# spectrum.net
KiCad netlist of a schematic drawn in EAGLE
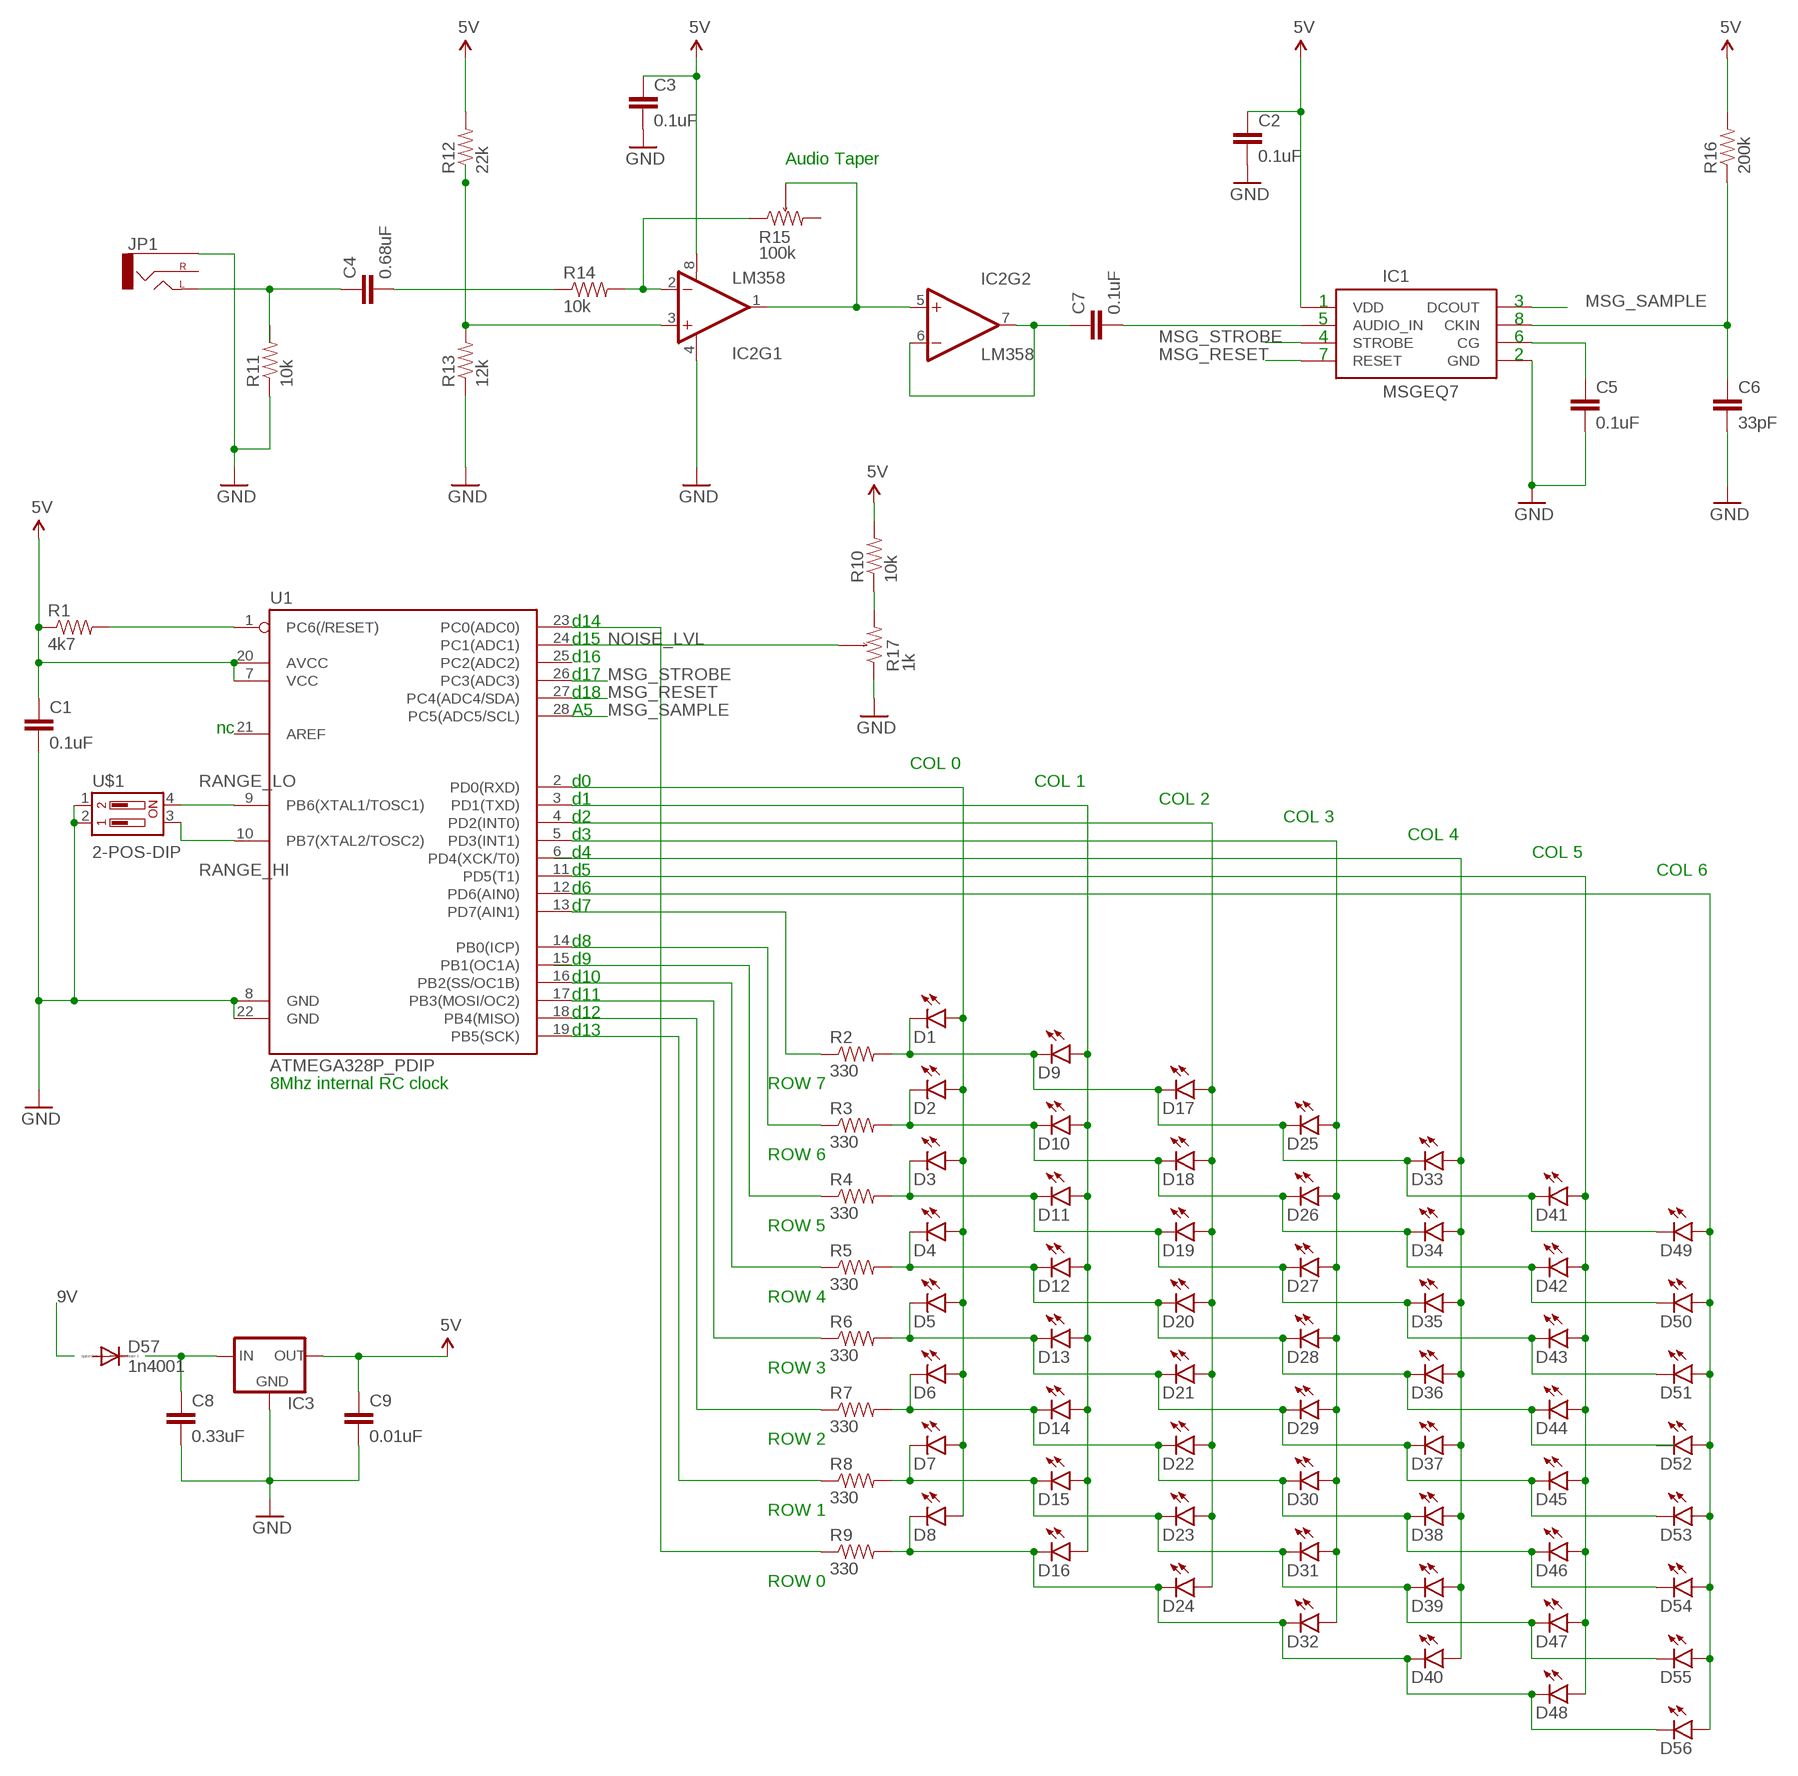
[diagram p0: schematic, sheet 1]

(export (version "E")
  (design (tool "Eeschema 10.0.6"))
  (components
    (comp (ref "C1")
      (value "0.1uF")
      (footprint "eagle-import:0402-CAP")
      (libsource (lib "eagle-import") (part "CAP0402-CAP"))
    )
    (comp (ref "C2")
      (value "0.1uF")
      (footprint "eagle-import:0402-CAP")
      (libsource (lib "eagle-import") (part "CAP0402-CAP"))
    )
    (comp (ref "C3")
      (value "0.1uF")
      (footprint "eagle-import:0402-CAP")
      (libsource (lib "eagle-import") (part "CAP0402-CAP"))
    )
    (comp (ref "C4")
      (value "0.68uF")
      (footprint "eagle-import:0402-CAP")
      (libsource (lib "eagle-import") (part "CAP0402-CAP"))
    )
    (comp (ref "C5")
      (value "0.1uF")
      (footprint "eagle-import:0402-CAP")
      (libsource (lib "eagle-import") (part "CAP0402-CAP"))
    )
    (comp (ref "C6")
      (value "33pF")
      (footprint "eagle-import:0402-CAP")
      (libsource (lib "eagle-import") (part "CAP0402-CAP"))
    )
    (comp (ref "C7")
      (value "0.1uF")
      (footprint "eagle-import:0402-CAP")
      (libsource (lib "eagle-import") (part "CAP0402-CAP"))
    )
    (comp (ref "C8")
      (value "0.33uF")
      (footprint "eagle-import:0402-CAP")
      (libsource (lib "eagle-import") (part "CAP0402-CAP"))
    )
    (comp (ref "C9")
      (value "0.01uF")
      (footprint "eagle-import:0402-CAP")
      (libsource (lib "eagle-import") (part "CAP0402-CAP"))
    )
    (comp (ref "D1")
      (value "LED5MM")
      (footprint "eagle-import:LED5MM")
      (libsource (lib "eagle-import") (part "LED5MM"))
    )
    (comp (ref "D2")
      (value "LED5MM")
      (footprint "eagle-import:LED5MM")
      (libsource (lib "eagle-import") (part "LED5MM"))
    )
    (comp (ref "D3")
      (value "LED5MM")
      (footprint "eagle-import:LED5MM")
      (libsource (lib "eagle-import") (part "LED5MM"))
    )
    (comp (ref "D4")
      (value "LED5MM")
      (footprint "eagle-import:LED5MM")
      (libsource (lib "eagle-import") (part "LED5MM"))
    )
    (comp (ref "D5")
      (value "LED5MM")
      (footprint "eagle-import:LED5MM")
      (libsource (lib "eagle-import") (part "LED5MM"))
    )
    (comp (ref "D6")
      (value "LED5MM")
      (footprint "eagle-import:LED5MM")
      (libsource (lib "eagle-import") (part "LED5MM"))
    )
    (comp (ref "D7")
      (value "LED5MM")
      (footprint "eagle-import:LED5MM")
      (libsource (lib "eagle-import") (part "LED5MM"))
    )
    (comp (ref "D8")
      (value "LED5MM")
      (footprint "eagle-import:LED5MM")
      (libsource (lib "eagle-import") (part "LED5MM"))
    )
    (comp (ref "D9")
      (value "LED5MM")
      (footprint "eagle-import:LED5MM")
      (libsource (lib "eagle-import") (part "LED5MM"))
    )
    (comp (ref "D10")
      (value "LED5MM")
      (footprint "eagle-import:LED5MM")
      (libsource (lib "eagle-import") (part "LED5MM"))
    )
    (comp (ref "D11")
      (value "LED5MM")
      (footprint "eagle-import:LED5MM")
      (libsource (lib "eagle-import") (part "LED5MM"))
    )
    (comp (ref "D12")
      (value "LED5MM")
      (footprint "eagle-import:LED5MM")
      (libsource (lib "eagle-import") (part "LED5MM"))
    )
    (comp (ref "D13")
      (value "LED5MM")
      (footprint "eagle-import:LED5MM")
      (libsource (lib "eagle-import") (part "LED5MM"))
    )
    (comp (ref "D14")
      (value "LED5MM")
      (footprint "eagle-import:LED5MM")
      (libsource (lib "eagle-import") (part "LED5MM"))
    )
    (comp (ref "D15")
      (value "LED5MM")
      (footprint "eagle-import:LED5MM")
      (libsource (lib "eagle-import") (part "LED5MM"))
    )
    (comp (ref "D16")
      (value "LED5MM")
      (footprint "eagle-import:LED5MM")
      (libsource (lib "eagle-import") (part "LED5MM"))
    )
    (comp (ref "D17")
      (value "LED5MM")
      (footprint "eagle-import:LED5MM")
      (libsource (lib "eagle-import") (part "LED5MM"))
    )
    (comp (ref "D18")
      (value "LED5MM")
      (footprint "eagle-import:LED5MM")
      (libsource (lib "eagle-import") (part "LED5MM"))
    )
    (comp (ref "D19")
      (value "LED5MM")
      (footprint "eagle-import:LED5MM")
      (libsource (lib "eagle-import") (part "LED5MM"))
    )
    (comp (ref "D20")
      (value "LED5MM")
      (footprint "eagle-import:LED5MM")
      (libsource (lib "eagle-import") (part "LED5MM"))
    )
    (comp (ref "D21")
      (value "LED5MM")
      (footprint "eagle-import:LED5MM")
      (libsource (lib "eagle-import") (part "LED5MM"))
    )
    (comp (ref "D22")
      (value "LED5MM")
      (footprint "eagle-import:LED5MM")
      (libsource (lib "eagle-import") (part "LED5MM"))
    )
    (comp (ref "D23")
      (value "LED5MM")
      (footprint "eagle-import:LED5MM")
      (libsource (lib "eagle-import") (part "LED5MM"))
    )
    (comp (ref "D24")
      (value "LED5MM")
      (footprint "eagle-import:LED5MM")
      (libsource (lib "eagle-import") (part "LED5MM"))
    )
    (comp (ref "D25")
      (value "LED5MM")
      (footprint "eagle-import:LED5MM")
      (libsource (lib "eagle-import") (part "LED5MM"))
    )
    (comp (ref "D26")
      (value "LED5MM")
      (footprint "eagle-import:LED5MM")
      (libsource (lib "eagle-import") (part "LED5MM"))
    )
    (comp (ref "D27")
      (value "LED5MM")
      (footprint "eagle-import:LED5MM")
      (libsource (lib "eagle-import") (part "LED5MM"))
    )
    (comp (ref "D28")
      (value "LED5MM")
      (footprint "eagle-import:LED5MM")
      (libsource (lib "eagle-import") (part "LED5MM"))
    )
    (comp (ref "D29")
      (value "LED5MM")
      (footprint "eagle-import:LED5MM")
      (libsource (lib "eagle-import") (part "LED5MM"))
    )
    (comp (ref "D30")
      (value "LED5MM")
      (footprint "eagle-import:LED5MM")
      (libsource (lib "eagle-import") (part "LED5MM"))
    )
    (comp (ref "D31")
      (value "LED5MM")
      (footprint "eagle-import:LED5MM")
      (libsource (lib "eagle-import") (part "LED5MM"))
    )
    (comp (ref "D32")
      (value "LED5MM")
      (footprint "eagle-import:LED5MM")
      (libsource (lib "eagle-import") (part "LED5MM"))
    )
    (comp (ref "D33")
      (value "LED5MM")
      (footprint "eagle-import:LED5MM")
      (libsource (lib "eagle-import") (part "LED5MM"))
    )
    (comp (ref "D34")
      (value "LED5MM")
      (footprint "eagle-import:LED5MM")
      (libsource (lib "eagle-import") (part "LED5MM"))
    )
    (comp (ref "D35")
      (value "LED5MM")
      (footprint "eagle-import:LED5MM")
      (libsource (lib "eagle-import") (part "LED5MM"))
    )
    (comp (ref "D36")
      (value "LED5MM")
      (footprint "eagle-import:LED5MM")
      (libsource (lib "eagle-import") (part "LED5MM"))
    )
    (comp (ref "D37")
      (value "LED5MM")
      (footprint "eagle-import:LED5MM")
      (libsource (lib "eagle-import") (part "LED5MM"))
    )
    (comp (ref "D38")
      (value "LED5MM")
      (footprint "eagle-import:LED5MM")
      (libsource (lib "eagle-import") (part "LED5MM"))
    )
    (comp (ref "D39")
      (value "LED5MM")
      (footprint "eagle-import:LED5MM")
      (libsource (lib "eagle-import") (part "LED5MM"))
    )
    (comp (ref "D40")
      (value "LED5MM")
      (footprint "eagle-import:LED5MM")
      (libsource (lib "eagle-import") (part "LED5MM"))
    )
    (comp (ref "D41")
      (value "LED5MM")
      (footprint "eagle-import:LED5MM")
      (libsource (lib "eagle-import") (part "LED5MM"))
    )
    (comp (ref "D42")
      (value "LED5MM")
      (footprint "eagle-import:LED5MM")
      (libsource (lib "eagle-import") (part "LED5MM"))
    )
    (comp (ref "D43")
      (value "LED5MM")
      (footprint "eagle-import:LED5MM")
      (libsource (lib "eagle-import") (part "LED5MM"))
    )
    (comp (ref "D44")
      (value "LED5MM")
      (footprint "eagle-import:LED5MM")
      (libsource (lib "eagle-import") (part "LED5MM"))
    )
    (comp (ref "D45")
      (value "LED5MM")
      (footprint "eagle-import:LED5MM")
      (libsource (lib "eagle-import") (part "LED5MM"))
    )
    (comp (ref "D46")
      (value "LED5MM")
      (footprint "eagle-import:LED5MM")
      (libsource (lib "eagle-import") (part "LED5MM"))
    )
    (comp (ref "D47")
      (value "LED5MM")
      (footprint "eagle-import:LED5MM")
      (libsource (lib "eagle-import") (part "LED5MM"))
    )
    (comp (ref "D48")
      (value "LED5MM")
      (footprint "eagle-import:LED5MM")
      (libsource (lib "eagle-import") (part "LED5MM"))
    )
    (comp (ref "D49")
      (value "LED5MM")
      (footprint "eagle-import:LED5MM")
      (libsource (lib "eagle-import") (part "LED5MM"))
    )
    (comp (ref "D50")
      (value "LED5MM")
      (footprint "eagle-import:LED5MM")
      (libsource (lib "eagle-import") (part "LED5MM"))
    )
    (comp (ref "D51")
      (value "LED5MM")
      (footprint "eagle-import:LED5MM")
      (libsource (lib "eagle-import") (part "LED5MM"))
    )
    (comp (ref "D52")
      (value "LED5MM")
      (footprint "eagle-import:LED5MM")
      (libsource (lib "eagle-import") (part "LED5MM"))
    )
    (comp (ref "D53")
      (value "LED5MM")
      (footprint "eagle-import:LED5MM")
      (libsource (lib "eagle-import") (part "LED5MM"))
    )
    (comp (ref "D54")
      (value "LED5MM")
      (footprint "eagle-import:LED5MM")
      (libsource (lib "eagle-import") (part "LED5MM"))
    )
    (comp (ref "D55")
      (value "LED5MM")
      (footprint "eagle-import:LED5MM")
      (libsource (lib "eagle-import") (part "LED5MM"))
    )
    (comp (ref "D56")
      (value "LED5MM")
      (footprint "eagle-import:LED5MM")
      (libsource (lib "eagle-import") (part "LED5MM"))
    )
    (comp (ref "D57")
      (value "1n4001")
      (footprint "eagle-import:DO41-10")
      (libsource (lib "eagle-import") (part "1N4004"))
    )
    (comp (ref "IC1")
      (value "MSGEQ7DIL")
      (footprint "eagle-import:DIL-08")
      (libsource (lib "eagle-import") (part "MSGEQ7DIL"))
    )
    (comp (ref "IC2")
      (value "LM358")
      (footprint "eagle-import:DIP08")
      (libsource (lib "eagle-import") (part "LM358"))
    )
    (comp (ref "IC3")
      (value "78LXX")
      (footprint "eagle-import:78LXX")
      (libsource (lib "eagle-import") (part "78LXX"))
    )
    (comp (ref "JP1")
      (value "AUDIO-JACK1:1")
      (footprint "eagle-import:STEREOJACK2.5MM")
      (libsource (lib "eagle-import") (part "AUDIO-JACK1{colon}1"))
    )
    (comp (ref "R1")
      (value "4k7")
      (footprint "eagle-import:0402-RES")
      (libsource (lib "eagle-import") (part "RESISTOR0402-RES"))
    )
    (comp (ref "R2")
      (value "330")
      (footprint "eagle-import:0402-RES")
      (libsource (lib "eagle-import") (part "RESISTOR0402-RES"))
    )
    (comp (ref "R3")
      (value "330")
      (footprint "eagle-import:0402-RES")
      (libsource (lib "eagle-import") (part "RESISTOR0402-RES"))
    )
    (comp (ref "R4")
      (value "330")
      (footprint "eagle-import:0402-RES")
      (libsource (lib "eagle-import") (part "RESISTOR0402-RES"))
    )
    (comp (ref "R5")
      (value "330")
      (footprint "eagle-import:0402-RES")
      (libsource (lib "eagle-import") (part "RESISTOR0402-RES"))
    )
    (comp (ref "R6")
      (value "330")
      (footprint "eagle-import:0402-RES")
      (libsource (lib "eagle-import") (part "RESISTOR0402-RES"))
    )
    (comp (ref "R7")
      (value "330")
      (footprint "eagle-import:0402-RES")
      (libsource (lib "eagle-import") (part "RESISTOR0402-RES"))
    )
    (comp (ref "R8")
      (value "330")
      (footprint "eagle-import:0402-RES")
      (libsource (lib "eagle-import") (part "RESISTOR0402-RES"))
    )
    (comp (ref "R9")
      (value "330")
      (footprint "eagle-import:0402-RES")
      (libsource (lib "eagle-import") (part "RESISTOR0402-RES"))
    )
    (comp (ref "R10")
      (value "10k")
      (footprint "eagle-import:0402-RES")
      (libsource (lib "eagle-import") (part "RESISTOR0402-RES"))
    )
    (comp (ref "R11")
      (value "10k")
      (footprint "eagle-import:0402-RES")
      (libsource (lib "eagle-import") (part "RESISTOR0402-RES"))
    )
    (comp (ref "R12")
      (value "22k")
      (footprint "eagle-import:0402-RES")
      (libsource (lib "eagle-import") (part "RESISTOR0402-RES"))
    )
    (comp (ref "R13")
      (value "12k")
      (footprint "eagle-import:0402-RES")
      (libsource (lib "eagle-import") (part "RESISTOR0402-RES"))
    )
    (comp (ref "R14")
      (value "10k")
      (footprint "eagle-import:0402-RES")
      (libsource (lib "eagle-import") (part "RESISTOR0402-RES"))
    )
    (comp (ref "R15")
      (value "100k")
      (footprint "eagle-import:0603-ARV")
      (libsource (lib "eagle-import") (part "POTENTIOMETER"))
    )
    (comp (ref "R16")
      (value "200k")
      (footprint "eagle-import:0402-RES")
      (libsource (lib "eagle-import") (part "RESISTOR0402-RES"))
    )
    (comp (ref "R17")
      (value "1k")
      (footprint "eagle-import:0603-ARV")
      (libsource (lib "eagle-import") (part "POTENTIOMETER"))
    )
    (comp (ref "U$1")
      (value "2-POS-DIP")
      (footprint "eagle-import:CHS-02A")
      (libsource (lib "eagle-import") (part "2-POS-DIP"))
    )
    (comp (ref "U1")
      (value "ATMEGA328P_PDIP")
      (footprint "eagle-import:DIL28-3")
      (libsource (lib "eagle-import") (part "ATMEGA328P_PDIP"))
    )
  )
  (nets
    (net (code "2") (name "/MSG_RESET") (class "Default")
      (node (ref "IC1") (pin "7") (pinfunction "RESET_7") (pintype "input"))
      (node (ref "U1") (pin "27") (pinfunction "PC4(ADC4/SDA)_27") (pintype "bidirectional"))
    )
    (net (code "3") (name "/MSG_SAMPLE") (class "Default")
      (node (ref "IC1") (pin "3") (pinfunction "DCOUT_3") (pintype "bidirectional"))
      (node (ref "U1") (pin "28") (pinfunction "PC5(ADC5/SCL)_28") (pintype "bidirectional"))
    )
    (net (code "4") (name "/MSG_STROBE") (class "Default")
      (node (ref "IC1") (pin "4") (pinfunction "STROBE_4") (pintype "input"))
      (node (ref "U1") (pin "26") (pinfunction "PC3(ADC3)_26") (pintype "bidirectional"))
    )
    (net (code "5") (name "/NOISE_LVL") (class "Default")
      (node (ref "R17") (pin "3") (pinfunction "P$1_3") (pintype "bidirectional"))
      (node (ref "R17") (pin "4") (pinfunction "P$1_4") (pintype "bidirectional"))
      (node (ref "R17") (pin "5") (pinfunction "P$1_5") (pintype "bidirectional"))
      (node (ref "R17") (pin "6") (pinfunction "P$1_6") (pintype "bidirectional"))
      (node (ref "R17") (pin "7") (pinfunction "P$1_7") (pintype "bidirectional"))
      (node (ref "R17") (pin "8") (pinfunction "P$1_8") (pintype "bidirectional"))
      (node (ref "U1") (pin "24") (pinfunction "PC1(ADC1)_24") (pintype "bidirectional"))
    )
    (net (code "6") (name "/RANGE_HI") (class "Default")
      (node (ref "U$1") (pin "3") (pinfunction "P$3_3") (pintype "bidirectional"))
      (node (ref "U1") (pin "10") (pinfunction "PB7(XTAL2/TOSC2)_10") (pintype "bidirectional"))
    )
    (net (code "7") (name "/RANGE_LO") (class "Default")
      (node (ref "U$1") (pin "4") (pinfunction "P$4_4") (pintype "bidirectional"))
      (node (ref "U1") (pin "9") (pinfunction "PB6(XTAL1/TOSC1)_9") (pintype "bidirectional"))
    )
    (net (code "8") (name "5V") (class "Default")
      (node (ref "C1") (pin "1") (pinfunction "1_1") (pintype "passive"))
      (node (ref "C2") (pin "1") (pinfunction "1_1") (pintype "passive"))
      (node (ref "C3") (pin "1") (pinfunction "1_1") (pintype "passive"))
      (node (ref "C9") (pin "1") (pinfunction "1_1") (pintype "passive"))
      (node (ref "IC1") (pin "1") (pinfunction "VDD_1") (pintype "input"))
      (node (ref "IC2") (pin "8") (pinfunction "V+_8") (pintype "power_in"))
      (node (ref "IC3") (pin "OUT") (pinfunction "OUT_OUT") (pintype "passive"))
      (node (ref "R1") (pin "1") (pinfunction "1_1") (pintype "passive"))
      (node (ref "R10") (pin "2") (pinfunction "2_2") (pintype "passive"))
      (node (ref "R12") (pin "2") (pinfunction "2_2") (pintype "passive"))
      (node (ref "R16") (pin "2") (pinfunction "2_2") (pintype "passive"))
      (node (ref "U1") (pin "20") (pinfunction "AVCC_20") (pintype "bidirectional"))
      (node (ref "U1") (pin "7") (pinfunction "VCC_7") (pintype "bidirectional"))
    )
    (net (code "9") (name "GND") (class "Default")
      (node (ref "C1") (pin "2") (pinfunction "2_2") (pintype "passive"))
      (node (ref "C2") (pin "2") (pinfunction "2_2") (pintype "passive"))
      (node (ref "C3") (pin "2") (pinfunction "2_2") (pintype "passive"))
      (node (ref "C5") (pin "2") (pinfunction "2_2") (pintype "passive"))
      (node (ref "C6") (pin "2") (pinfunction "2_2") (pintype "passive"))
      (node (ref "C8") (pin "2") (pinfunction "2_2") (pintype "passive"))
      (node (ref "C9") (pin "2") (pinfunction "2_2") (pintype "passive"))
      (node (ref "IC1") (pin "2") (pinfunction "GND_2") (pintype "bidirectional"))
      (node (ref "IC2") (pin "4") (pinfunction "V-_4") (pintype "power_in"))
      (node (ref "IC3") (pin "GND") (pinfunction "GND_GND") (pintype "input"))
      (node (ref "JP1") (pin "5") (pinfunction "SLEEVE_5") (pintype "bidirectional"))
      (node (ref "R11") (pin "1") (pinfunction "1_1") (pintype "passive"))
      (node (ref "R13") (pin "1") (pinfunction "1_1") (pintype "passive"))
      (node (ref "R17") (pin "1") (pinfunction "1_1") (pintype "passive"))
      (node (ref "U$1") (pin "1") (pinfunction "P$1_1") (pintype "bidirectional"))
      (node (ref "U$1") (pin "2") (pinfunction "P$2_2") (pintype "bidirectional"))
      (node (ref "U1") (pin "22") (pinfunction "GND_22") (pintype "bidirectional"))
      (node (ref "U1") (pin "8") (pinfunction "GND_8") (pintype "bidirectional"))
    )
    (net (code "10") (name "Net-(C4-Pad2)") (class "Default")
      (node (ref "C4") (pin "2") (pinfunction "2_2") (pintype "passive"))
      (node (ref "R14") (pin "1") (pinfunction "1_1") (pintype "passive"))
    )
    (net (code "11") (name "Net-(C8-Pad1)") (class "Default")
      (node (ref "C8") (pin "1") (pinfunction "1_1") (pintype "passive"))
      (node (ref "IC3") (pin "IN") (pinfunction "IN_IN") (pintype "input"))
    )
    (net (code "12") (name "Net-(D1-C)") (class "Default")
      (node (ref "D1") (pin "K") (pinfunction "C_K") (pintype "passive"))
      (node (ref "D17") (pin "K") (pinfunction "C_K") (pintype "passive"))
      (node (ref "D25") (pin "K") (pinfunction "C_K") (pintype "passive"))
      (node (ref "D33") (pin "K") (pinfunction "C_K") (pintype "passive"))
      (node (ref "D41") (pin "K") (pinfunction "C_K") (pintype "passive"))
      (node (ref "D49") (pin "K") (pinfunction "C_K") (pintype "passive"))
      (node (ref "D9") (pin "K") (pinfunction "C_K") (pintype "passive"))
      (node (ref "R2") (pin "2") (pinfunction "2_2") (pintype "passive"))
    )
    (net (code "13") (name "Net-(D10-C)") (class "Default")
      (node (ref "D10") (pin "K") (pinfunction "C_K") (pintype "passive"))
      (node (ref "D18") (pin "K") (pinfunction "C_K") (pintype "passive"))
      (node (ref "D2") (pin "K") (pinfunction "C_K") (pintype "passive"))
      (node (ref "D26") (pin "K") (pinfunction "C_K") (pintype "passive"))
      (node (ref "D34") (pin "K") (pinfunction "C_K") (pintype "passive"))
      (node (ref "D42") (pin "K") (pinfunction "C_K") (pintype "passive"))
      (node (ref "D50") (pin "K") (pinfunction "C_K") (pintype "passive"))
      (node (ref "R3") (pin "2") (pinfunction "2_2") (pintype "passive"))
    )
    (net (code "14") (name "Net-(D11-C)") (class "Default")
      (node (ref "D11") (pin "K") (pinfunction "C_K") (pintype "passive"))
      (node (ref "D19") (pin "K") (pinfunction "C_K") (pintype "passive"))
      (node (ref "D27") (pin "K") (pinfunction "C_K") (pintype "passive"))
      (node (ref "D3") (pin "K") (pinfunction "C_K") (pintype "passive"))
      (node (ref "D35") (pin "K") (pinfunction "C_K") (pintype "passive"))
      (node (ref "D43") (pin "K") (pinfunction "C_K") (pintype "passive"))
      (node (ref "D51") (pin "K") (pinfunction "C_K") (pintype "passive"))
      (node (ref "R4") (pin "2") (pinfunction "2_2") (pintype "passive"))
    )
    (net (code "15") (name "Net-(D12-C)") (class "Default")
      (node (ref "D12") (pin "K") (pinfunction "C_K") (pintype "passive"))
      (node (ref "D20") (pin "K") (pinfunction "C_K") (pintype "passive"))
      (node (ref "D28") (pin "K") (pinfunction "C_K") (pintype "passive"))
      (node (ref "D36") (pin "K") (pinfunction "C_K") (pintype "passive"))
      (node (ref "D4") (pin "K") (pinfunction "C_K") (pintype "passive"))
      (node (ref "D44") (pin "K") (pinfunction "C_K") (pintype "passive"))
      (node (ref "R5") (pin "2") (pinfunction "2_2") (pintype "passive"))
    )
    (net (code "16") (name "Net-(D13-C)") (class "Default")
      (node (ref "D13") (pin "K") (pinfunction "C_K") (pintype "passive"))
      (node (ref "D21") (pin "K") (pinfunction "C_K") (pintype "passive"))
      (node (ref "D29") (pin "K") (pinfunction "C_K") (pintype "passive"))
      (node (ref "D37") (pin "K") (pinfunction "C_K") (pintype "passive"))
      (node (ref "D45") (pin "K") (pinfunction "C_K") (pintype "passive"))
      (node (ref "D5") (pin "K") (pinfunction "C_K") (pintype "passive"))
      (node (ref "D53") (pin "K") (pinfunction "C_K") (pintype "passive"))
      (node (ref "R6") (pin "2") (pinfunction "2_2") (pintype "passive"))
    )
    (net (code "17") (name "Net-(D14-C)") (class "Default")
      (node (ref "D14") (pin "K") (pinfunction "C_K") (pintype "passive"))
      (node (ref "D22") (pin "K") (pinfunction "C_K") (pintype "passive"))
      (node (ref "D30") (pin "K") (pinfunction "C_K") (pintype "passive"))
      (node (ref "D38") (pin "K") (pinfunction "C_K") (pintype "passive"))
      (node (ref "D46") (pin "K") (pinfunction "C_K") (pintype "passive"))
      (node (ref "D54") (pin "K") (pinfunction "C_K") (pintype "passive"))
      (node (ref "D6") (pin "K") (pinfunction "C_K") (pintype "passive"))
      (node (ref "R7") (pin "2") (pinfunction "2_2") (pintype "passive"))
    )
    (net (code "18") (name "Net-(D15-C)") (class "Default")
      (node (ref "D15") (pin "K") (pinfunction "C_K") (pintype "passive"))
      (node (ref "D23") (pin "K") (pinfunction "C_K") (pintype "passive"))
      (node (ref "D31") (pin "K") (pinfunction "C_K") (pintype "passive"))
      (node (ref "D39") (pin "K") (pinfunction "C_K") (pintype "passive"))
      (node (ref "D47") (pin "K") (pinfunction "C_K") (pintype "passive"))
      (node (ref "D55") (pin "K") (pinfunction "C_K") (pintype "passive"))
      (node (ref "D7") (pin "K") (pinfunction "C_K") (pintype "passive"))
      (node (ref "R8") (pin "2") (pinfunction "2_2") (pintype "passive"))
    )
    (net (code "19") (name "Net-(D16-C)") (class "Default")
      (node (ref "D16") (pin "K") (pinfunction "C_K") (pintype "passive"))
      (node (ref "D24") (pin "K") (pinfunction "C_K") (pintype "passive"))
      (node (ref "D32") (pin "K") (pinfunction "C_K") (pintype "passive"))
      (node (ref "D40") (pin "K") (pinfunction "C_K") (pintype "passive"))
      (node (ref "D48") (pin "K") (pinfunction "C_K") (pintype "passive"))
      (node (ref "D56") (pin "K") (pinfunction "C_K") (pintype "passive"))
      (node (ref "D8") (pin "K") (pinfunction "C_K") (pintype "passive"))
      (node (ref "R9") (pin "2") (pinfunction "2_2") (pintype "passive"))
    )
    (net (code "20") (name "Net-(D33-PadA)") (class "Default")
      (node (ref "D33") (pin "A") (pinfunction "A_A") (pintype "passive"))
      (node (ref "D34") (pin "A") (pinfunction "A_A") (pintype "passive"))
      (node (ref "D35") (pin "A") (pinfunction "A_A") (pintype "passive"))
      (node (ref "D36") (pin "A") (pinfunction "A_A") (pintype "passive"))
      (node (ref "D37") (pin "A") (pinfunction "A_A") (pintype "passive"))
      (node (ref "D38") (pin "A") (pinfunction "A_A") (pintype "passive"))
      (node (ref "D39") (pin "A") (pinfunction "A_A") (pintype "passive"))
      (node (ref "D40") (pin "A") (pinfunction "A_A") (pintype "passive"))
    )
    (net (code "21") (name "Net-(IC1-AUDIO_IN)") (class "Default")
      (node (ref "C7") (pin "2") (pinfunction "2_2") (pintype "passive"))
      (node (ref "IC1") (pin "5") (pinfunction "AUDIO_IN_5") (pintype "input"))
    )
    (net (code "22") (name "Net-(IC1-CG)") (class "Default")
      (node (ref "C5") (pin "1") (pinfunction "1_1") (pintype "passive"))
      (node (ref "IC1") (pin "6") (pinfunction "CG_6") (pintype "bidirectional"))
    )
    (net (code "23") (name "Net-(IC1-CKIN)") (class "Default")
      (node (ref "C6") (pin "1") (pinfunction "1_1") (pintype "passive"))
      (node (ref "IC1") (pin "8") (pinfunction "CKIN_8") (pintype "bidirectional"))
      (node (ref "R16") (pin "1") (pinfunction "1_1") (pintype "passive"))
    )
    (net (code "24") (name "Net-(IC2A-+IN)") (class "Default")
      (node (ref "IC2") (pin "3") (pinfunction "+IN_3") (pintype "input"))
      (node (ref "R12") (pin "1") (pinfunction "1_1") (pintype "passive"))
      (node (ref "R13") (pin "2") (pinfunction "2_2") (pintype "passive"))
    )
    (net (code "25") (name "Net-(IC2A--IN)") (class "Default")
      (node (ref "IC2") (pin "2") (pinfunction "-IN_2") (pintype "input"))
      (node (ref "R14") (pin "2") (pinfunction "2_2") (pintype "passive"))
      (node (ref "R15") (pin "1") (pinfunction "1_1") (pintype "passive"))
    )
    (net (code "26") (name "Net-(IC2A-OUT)") (class "Default")
      (node (ref "IC2") (pin "1") (pinfunction "OUT_1") (pintype "output"))
      (node (ref "IC2") (pin "5") (pinfunction "+IN_5") (pintype "input"))
      (node (ref "R15") (pin "3") (pinfunction "P$1_3") (pintype "bidirectional"))
      (node (ref "R15") (pin "4") (pinfunction "P$1_4") (pintype "bidirectional"))
      (node (ref "R15") (pin "5") (pinfunction "P$1_5") (pintype "bidirectional"))
      (node (ref "R15") (pin "6") (pinfunction "P$1_6") (pintype "bidirectional"))
      (node (ref "R15") (pin "7") (pinfunction "P$1_7") (pintype "bidirectional"))
      (node (ref "R15") (pin "8") (pinfunction "P$1_8") (pintype "bidirectional"))
    )
    (net (code "27") (name "Net-(IC2B--IN)") (class "Default")
      (node (ref "C7") (pin "1") (pinfunction "1_1") (pintype "passive"))
      (node (ref "IC2") (pin "6") (pinfunction "-IN_6") (pintype "input"))
      (node (ref "IC2") (pin "7") (pinfunction "OUT_7") (pintype "output"))
    )
    (net (code "28") (name "Net-(JP1-LEFT)") (class "Default")
      (node (ref "C4") (pin "1") (pinfunction "1_1") (pintype "passive"))
      (node (ref "JP1") (pin "1") (pinfunction "LEFT_1") (pintype "bidirectional"))
    )
    (net (code "29") (name "Net-(R10-Pad1)") (class "Default")
      (node (ref "R10") (pin "1") (pinfunction "1_1") (pintype "passive"))
      (node (ref "R17") (pin "2") (pinfunction "2_2") (pintype "passive"))
    )
    (net (code "30") (name "Net-(U1-PB0(ICP))") (class "Default")
      (node (ref "R3") (pin "1") (pinfunction "1_1") (pintype "passive"))
      (node (ref "U1") (pin "14") (pinfunction "PB0(ICP)_14") (pintype "bidirectional"))
    )
    (net (code "31") (name "Net-(U1-PB2(SS{slash}OC1B))") (class "Default")
      (node (ref "R5") (pin "1") (pinfunction "1_1") (pintype "passive"))
      (node (ref "U1") (pin "16") (pinfunction "PB2(SS/OC1B)_16") (pintype "bidirectional"))
    )
    (net (code "32") (name "Net-(U1-PB3(MOSI{slash}OC2))") (class "Default")
      (node (ref "R6") (pin "1") (pinfunction "1_1") (pintype "passive"))
      (node (ref "U1") (pin "17") (pinfunction "PB3(MOSI/OC2)_17") (pintype "bidirectional"))
    )
    (net (code "33") (name "Net-(U1-PB4(MISO))") (class "Default")
      (node (ref "R7") (pin "1") (pinfunction "1_1") (pintype "passive"))
      (node (ref "U1") (pin "18") (pinfunction "PB4(MISO)_18") (pintype "bidirectional"))
    )
    (net (code "34") (name "Net-(U1-PB5(SCK))") (class "Default")
      (node (ref "R8") (pin "1") (pinfunction "1_1") (pintype "passive"))
      (node (ref "U1") (pin "19") (pinfunction "PB5(SCK)_19") (pintype "bidirectional"))
    )
    (net (code "35") (name "Net-(U1-PC0(ADC0))") (class "Default")
      (node (ref "R9") (pin "1") (pinfunction "1_1") (pintype "passive"))
      (node (ref "U1") (pin "23") (pinfunction "PC0(ADC0)_23") (pintype "bidirectional"))
    )
    (net (code "36") (name "Net-(U1-PC6({slash}RESET))") (class "Default")
      (node (ref "R1") (pin "2") (pinfunction "2_2") (pintype "passive"))
      (node (ref "U1") (pin "1") (pinfunction "PC6(/RESET)_1") (pintype "bidirectional"))
    )
    (net (code "37") (name "Net-(U1-PD0(RXD))") (class "Default")
      (node (ref "D1") (pin "A") (pinfunction "A_A") (pintype "passive"))
      (node (ref "D2") (pin "A") (pinfunction "A_A") (pintype "passive"))
      (node (ref "D3") (pin "A") (pinfunction "A_A") (pintype "passive"))
      (node (ref "D4") (pin "A") (pinfunction "A_A") (pintype "passive"))
      (node (ref "D5") (pin "A") (pinfunction "A_A") (pintype "passive"))
      (node (ref "D6") (pin "A") (pinfunction "A_A") (pintype "passive"))
      (node (ref "D7") (pin "A") (pinfunction "A_A") (pintype "passive"))
      (node (ref "D8") (pin "A") (pinfunction "A_A") (pintype "passive"))
      (node (ref "U1") (pin "2") (pinfunction "PD0(RXD)_2") (pintype "bidirectional"))
    )
    (net (code "38") (name "Net-(U1-PD1(TXD))") (class "Default")
      (node (ref "D10") (pin "A") (pinfunction "A_A") (pintype "passive"))
      (node (ref "D11") (pin "A") (pinfunction "A_A") (pintype "passive"))
      (node (ref "D12") (pin "A") (pinfunction "A_A") (pintype "passive"))
      (node (ref "D13") (pin "A") (pinfunction "A_A") (pintype "passive"))
      (node (ref "D14") (pin "A") (pinfunction "A_A") (pintype "passive"))
      (node (ref "D15") (pin "A") (pinfunction "A_A") (pintype "passive"))
      (node (ref "D16") (pin "A") (pinfunction "A_A") (pintype "passive"))
      (node (ref "D9") (pin "A") (pinfunction "A_A") (pintype "passive"))
      (node (ref "U1") (pin "3") (pinfunction "PD1(TXD)_3") (pintype "bidirectional"))
    )
    (net (code "39") (name "Net-(U1-PD2(INT0))") (class "Default")
      (node (ref "D17") (pin "A") (pinfunction "A_A") (pintype "passive"))
      (node (ref "D18") (pin "A") (pinfunction "A_A") (pintype "passive"))
      (node (ref "D19") (pin "A") (pinfunction "A_A") (pintype "passive"))
      (node (ref "D20") (pin "A") (pinfunction "A_A") (pintype "passive"))
      (node (ref "D21") (pin "A") (pinfunction "A_A") (pintype "passive"))
      (node (ref "D22") (pin "A") (pinfunction "A_A") (pintype "passive"))
      (node (ref "D23") (pin "A") (pinfunction "A_A") (pintype "passive"))
      (node (ref "D24") (pin "A") (pinfunction "A_A") (pintype "passive"))
      (node (ref "U1") (pin "4") (pinfunction "PD2(INT0)_4") (pintype "bidirectional"))
    )
    (net (code "40") (name "Net-(U1-PD3(INT1))") (class "Default")
      (node (ref "D25") (pin "A") (pinfunction "A_A") (pintype "passive"))
      (node (ref "D26") (pin "A") (pinfunction "A_A") (pintype "passive"))
      (node (ref "D27") (pin "A") (pinfunction "A_A") (pintype "passive"))
      (node (ref "D28") (pin "A") (pinfunction "A_A") (pintype "passive"))
      (node (ref "D29") (pin "A") (pinfunction "A_A") (pintype "passive"))
      (node (ref "D30") (pin "A") (pinfunction "A_A") (pintype "passive"))
      (node (ref "D31") (pin "A") (pinfunction "A_A") (pintype "passive"))
      (node (ref "D32") (pin "A") (pinfunction "A_A") (pintype "passive"))
      (node (ref "U1") (pin "5") (pinfunction "PD3(INT1)_5") (pintype "bidirectional"))
    )
    (net (code "41") (name "Net-(U1-PD5(T1))") (class "Default")
      (node (ref "D41") (pin "A") (pinfunction "A_A") (pintype "passive"))
      (node (ref "D42") (pin "A") (pinfunction "A_A") (pintype "passive"))
      (node (ref "D43") (pin "A") (pinfunction "A_A") (pintype "passive"))
      (node (ref "D44") (pin "A") (pinfunction "A_A") (pintype "passive"))
      (node (ref "D45") (pin "A") (pinfunction "A_A") (pintype "passive"))
      (node (ref "D46") (pin "A") (pinfunction "A_A") (pintype "passive"))
      (node (ref "D47") (pin "A") (pinfunction "A_A") (pintype "passive"))
      (node (ref "D48") (pin "A") (pinfunction "A_A") (pintype "passive"))
      (node (ref "U1") (pin "11") (pinfunction "PD5(T1)_11") (pintype "bidirectional"))
    )
    (net (code "42") (name "Net-(U1-PD6(AIN0))") (class "Default")
      (node (ref "D49") (pin "A") (pinfunction "A_A") (pintype "passive"))
      (node (ref "D50") (pin "A") (pinfunction "A_A") (pintype "passive"))
      (node (ref "D51") (pin "A") (pinfunction "A_A") (pintype "passive"))
      (node (ref "D52") (pin "A") (pinfunction "A_A") (pintype "passive"))
      (node (ref "D53") (pin "A") (pinfunction "A_A") (pintype "passive"))
      (node (ref "D54") (pin "A") (pinfunction "A_A") (pintype "passive"))
      (node (ref "D55") (pin "A") (pinfunction "A_A") (pintype "passive"))
      (node (ref "D56") (pin "A") (pinfunction "A_A") (pintype "passive"))
      (node (ref "U1") (pin "12") (pinfunction "PD6(AIN0)_12") (pintype "bidirectional"))
    )
    (net (code "43") (name "Net-(U1-PD7(AIN1))") (class "Default")
      (node (ref "R2") (pin "1") (pinfunction "1_1") (pintype "passive"))
      (node (ref "U1") (pin "13") (pinfunction "PD7(AIN1)_13") (pintype "bidirectional"))
    )
    (net (code "44") (name "unconnected-(D52-C-PadK)") (class "Default")
      (node (ref "D52") (pin "K") (pinfunction "C_K") (pintype "passive"))
    )
    (net (code "45") (name "unconnected-(D57-PadA)") (class "Default")
      (node (ref "D57") (pin "A") (pinfunction "A_A") (pintype "passive"))
    )
    (net (code "46") (name "unconnected-(D57-PadC)") (class "Default")
      (node (ref "D57") (pin "C") (pinfunction "C_C") (pintype "passive"))
    )
    (net (code "47") (name "unconnected-(JP1-RIGHT-Pad4)") (class "Default")
      (node (ref "JP1") (pin "4") (pinfunction "RIGHT_4") (pintype "bidirectional"))
    )
    (net (code "48") (name "unconnected-(R4-Pad1)") (class "Default")
      (node (ref "R4") (pin "1") (pinfunction "1_1") (pintype "passive"))
    )
    (net (code "49") (name "unconnected-(R11-Pad2)") (class "Default")
      (node (ref "R11") (pin "2") (pinfunction "2_2") (pintype "passive"))
    )
    (net (code "50") (name "unconnected-(R15-Pad2)") (class "Default")
      (node (ref "R15") (pin "2") (pinfunction "2_2") (pintype "passive"))
    )
    (net (code "51") (name "unconnected-(U1-AREF-Pad21)") (class "Default")
      (node (ref "U1") (pin "21") (pinfunction "AREF_21") (pintype "bidirectional"))
    )
    (net (code "52") (name "unconnected-(U1-PB1(OC1A)-Pad15)") (class "Default")
      (node (ref "U1") (pin "15") (pinfunction "PB1(OC1A)_15") (pintype "bidirectional"))
    )
    (net (code "53") (name "unconnected-(U1-PC2(ADC2)-Pad25)") (class "Default")
      (node (ref "U1") (pin "25") (pinfunction "PC2(ADC2)_25") (pintype "bidirectional"))
    )
    (net (code "54") (name "unconnected-(U1-PD4(XCK{slash}T0)-Pad6)") (class "Default")
      (node (ref "U1") (pin "6") (pinfunction "PD4(XCK/T0)_6") (pintype "bidirectional"))
    )
  )
)
